# Fishboard.net
KiCad netlist of a schematic drawn in EAGLE
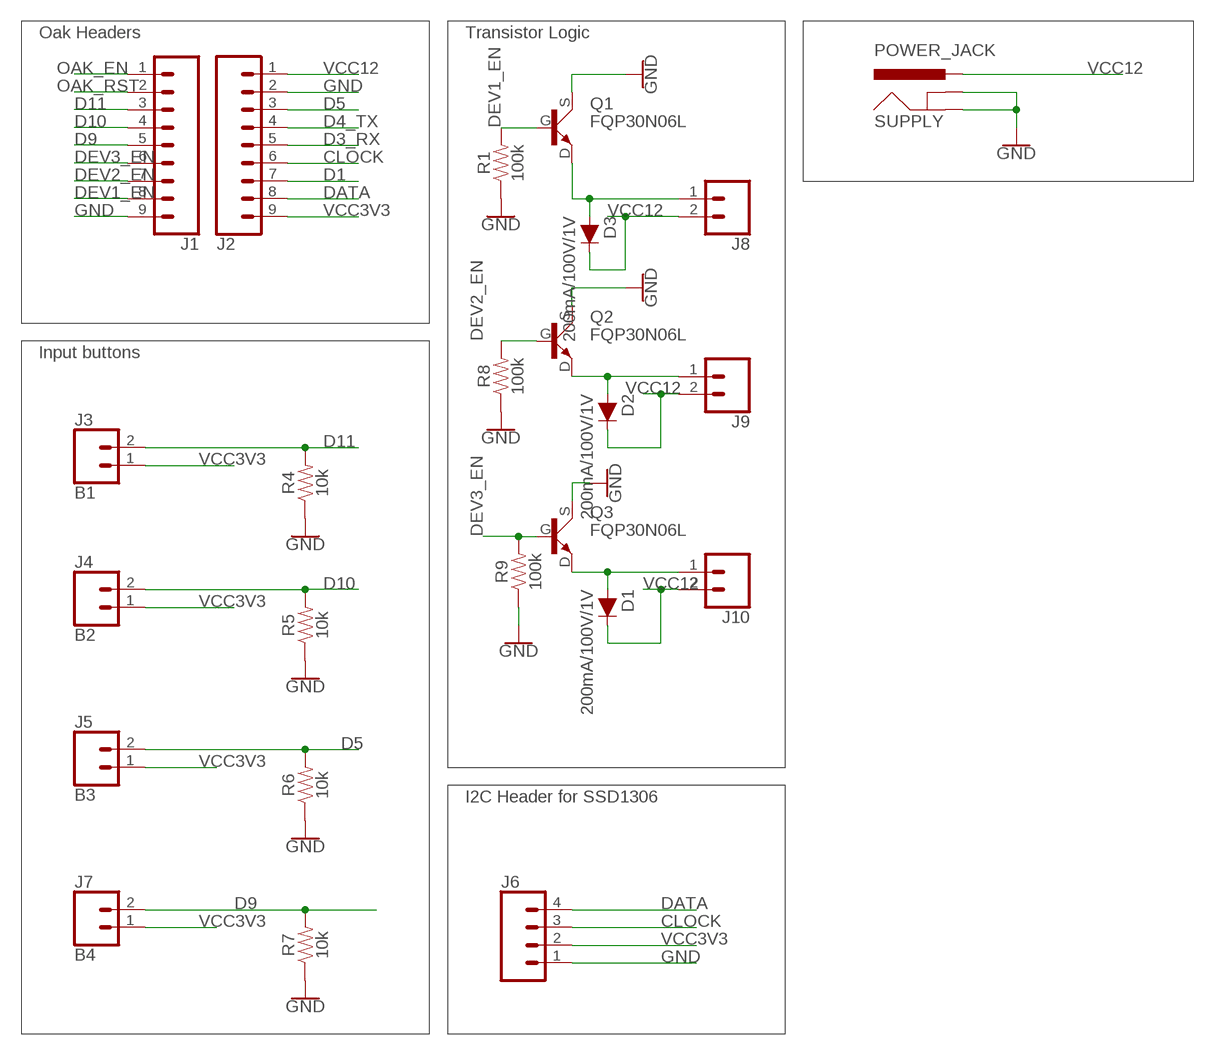
[diagram p0: schematic, sheet 1]

(export (version "E")
  (design (tool "Eeschema 10.0.6"))
  (components
    (comp (ref "D1")
      (value "200mA/100V/1V")
      (footprint "eagle-import:DIODE-1N4148-KIT")
      (libsource (lib "eagle-import") (part "DIODE-KIT"))
    )
    (comp (ref "D2")
      (value "200mA/100V/1V")
      (footprint "eagle-import:DIODE-1N4148-KIT")
      (libsource (lib "eagle-import") (part "DIODE-KIT"))
    )
    (comp (ref "D3")
      (value "200mA/100V/1V")
      (footprint "eagle-import:DIODE-1N4148-KIT")
      (libsource (lib "eagle-import") (part "DIODE-KIT"))
    )
    (comp (ref "J1")
      (value "CONN_09LOCK")
      (footprint "eagle-import:1X09_LOCK")
      (libsource (lib "eagle-import") (part "CONN_09LOCK"))
    )
    (comp (ref "J2")
      (value "CONN_09LOCK")
      (footprint "eagle-import:1X09_LOCK")
      (libsource (lib "eagle-import") (part "CONN_09LOCK"))
    )
    (comp (ref "J3")
      (value "B1")
      (footprint "eagle-import:1X02_LOCK")
      (libsource (lib "eagle-import") (part "CONN_02LOCK"))
    )
    (comp (ref "J4")
      (value "B2")
      (footprint "eagle-import:1X02_LOCK")
      (libsource (lib "eagle-import") (part "CONN_02LOCK"))
    )
    (comp (ref "J5")
      (value "B3")
      (footprint "eagle-import:1X02_LOCK")
      (libsource (lib "eagle-import") (part "CONN_02LOCK"))
    )
    (comp (ref "J6")
      (value "CONN_04LOCK")
      (footprint "eagle-import:1X04_LOCK")
      (libsource (lib "eagle-import") (part "CONN_04LOCK"))
    )
    (comp (ref "J7")
      (value "B4")
      (footprint "eagle-import:1X02_LOCK")
      (libsource (lib "eagle-import") (part "CONN_02LOCK"))
    )
    (comp (ref "J8")
      (value "CONN_02PTH3")
      (footprint "eagle-import:1X02_LONGPADS")
      (libsource (lib "eagle-import") (part "CONN_02PTH3"))
    )
    (comp (ref "J9")
      (value "CONN_02PTH3")
      (footprint "eagle-import:1X02_LONGPADS")
      (libsource (lib "eagle-import") (part "CONN_02PTH3"))
    )
    (comp (ref "J10")
      (value "CONN_02PTH3")
      (footprint "eagle-import:1X02_LONGPADS")
      (libsource (lib "eagle-import") (part "CONN_02PTH3"))
    )
    (comp (ref "Q1")
      (value "FQP30N06L")
      (footprint "eagle-import:TO220")
      (libsource (lib "eagle-import") (part "FQP30N06L"))
    )
    (comp (ref "Q2")
      (value "FQP30N06L")
      (footprint "eagle-import:TO220")
      (libsource (lib "eagle-import") (part "FQP30N06L"))
    )
    (comp (ref "Q3")
      (value "FQP30N06L")
      (footprint "eagle-import:TO220")
      (libsource (lib "eagle-import") (part "FQP30N06L"))
    )
    (comp (ref "R1")
      (value "100k")
      (footprint "eagle-import:AXIAL-0.3")
      (libsource (lib "eagle-import") (part "100KOHM-HORIZ-1/4W-5%"))
    )
    (comp (ref "R4")
      (value "10k")
      (footprint "eagle-import:AXIAL-0.3")
      (libsource (lib "eagle-import") (part "10KOHM-HORIZ-1/4W-1%"))
    )
    (comp (ref "R5")
      (value "10k")
      (footprint "eagle-import:AXIAL-0.3")
      (libsource (lib "eagle-import") (part "10KOHM-HORIZ-1/4W-1%"))
    )
    (comp (ref "R6")
      (value "10k")
      (footprint "eagle-import:AXIAL-0.3")
      (libsource (lib "eagle-import") (part "10KOHM-HORIZ-1/4W-1%"))
    )
    (comp (ref "R7")
      (value "10k")
      (footprint "eagle-import:AXIAL-0.3")
      (libsource (lib "eagle-import") (part "10KOHM-HORIZ-1/4W-1%"))
    )
    (comp (ref "R8")
      (value "100k")
      (footprint "eagle-import:AXIAL-0.3")
      (libsource (lib "eagle-import") (part "100KOHM-HORIZ-1/4W-5%"))
    )
    (comp (ref "R9")
      (value "100k")
      (footprint "eagle-import:AXIAL-0.3")
      (libsource (lib "eagle-import") (part "100KOHM-HORIZ-1/4W-5%"))
    )
    (comp (ref "SUPPLY")
      (value "POWER_JACK")
      (footprint "eagle-import:POWER_JACK_PTH")
      (libsource (lib "eagle-import") (part "POWER_JACK"))
    )
  )
  (nets
    (net (code "1") (name "/CLOCK") (class "Default")
      (node (ref "J2") (pin "6") (pinfunction "6_6") (pintype "passive"))
      (node (ref "J6") (pin "3") (pinfunction "3_3") (pintype "passive"))
    )
    (net (code "2") (name "/D1") (class "Default")
      (node (ref "J2") (pin "7") (pinfunction "7_7") (pintype "passive"))
    )
    (net (code "3") (name "/D3_RX") (class "Default")
      (node (ref "J2") (pin "5") (pinfunction "5_5") (pintype "passive"))
    )
    (net (code "4") (name "/D4_TX") (class "Default")
      (node (ref "J2") (pin "4") (pinfunction "4_4") (pintype "passive"))
    )
    (net (code "5") (name "/D5") (class "Default")
      (node (ref "J2") (pin "3") (pinfunction "3_3") (pintype "passive"))
      (node (ref "J5") (pin "2") (pinfunction "2_2") (pintype "passive"))
      (node (ref "R6") (pin "P$2") (pinfunction "2_P$2") (pintype "passive"))
    )
    (net (code "6") (name "/D9") (class "Default")
      (node (ref "J1") (pin "5") (pinfunction "5_5") (pintype "passive"))
      (node (ref "J7") (pin "2") (pinfunction "2_2") (pintype "passive"))
      (node (ref "R7") (pin "P$2") (pinfunction "2_P$2") (pintype "passive"))
    )
    (net (code "7") (name "/D10") (class "Default")
      (node (ref "J1") (pin "4") (pinfunction "4_4") (pintype "passive"))
      (node (ref "J4") (pin "2") (pinfunction "2_2") (pintype "passive"))
      (node (ref "R5") (pin "P$2") (pinfunction "2_P$2") (pintype "passive"))
    )
    (net (code "8") (name "/D11") (class "Default")
      (node (ref "J1") (pin "3") (pinfunction "3_3") (pintype "passive"))
      (node (ref "J3") (pin "2") (pinfunction "2_2") (pintype "passive"))
      (node (ref "R4") (pin "P$2") (pinfunction "2_P$2") (pintype "passive"))
    )
    (net (code "9") (name "/DATA") (class "Default")
      (node (ref "J2") (pin "8") (pinfunction "8_8") (pintype "passive"))
      (node (ref "J6") (pin "4") (pinfunction "4_4") (pintype "passive"))
    )
    (net (code "10") (name "/DEV1_EN") (class "Default")
      (node (ref "J1") (pin "8") (pinfunction "8_8") (pintype "passive"))
      (node (ref "Q1") (pin "G") (pinfunction "1_G") (pintype "passive"))
      (node (ref "R1") (pin "P$2") (pinfunction "2_P$2") (pintype "passive"))
    )
    (net (code "11") (name "/DEV2_EN") (class "Default")
      (node (ref "J1") (pin "7") (pinfunction "7_7") (pintype "passive"))
      (node (ref "Q2") (pin "G") (pinfunction "1_G") (pintype "passive"))
      (node (ref "R8") (pin "P$2") (pinfunction "2_P$2") (pintype "passive"))
    )
    (net (code "12") (name "/DEV3_EN") (class "Default")
      (node (ref "J1") (pin "6") (pinfunction "6_6") (pintype "passive"))
      (node (ref "Q3") (pin "G") (pinfunction "1_G") (pintype "passive"))
      (node (ref "R9") (pin "P$2") (pinfunction "2_P$2") (pintype "passive"))
    )
    (net (code "13") (name "/OAK_EN") (class "Default")
      (node (ref "J1") (pin "1") (pinfunction "1_1") (pintype "passive"))
    )
    (net (code "14") (name "/OAK_RST") (class "Default")
      (node (ref "J1") (pin "2") (pinfunction "2_2") (pintype "passive"))
    )
    (net (code "15") (name "/VCC3V3") (class "Default")
      (node (ref "J2") (pin "9") (pinfunction "9_9") (pintype "passive"))
      (node (ref "J3") (pin "1") (pinfunction "1_1") (pintype "passive"))
      (node (ref "J4") (pin "1") (pinfunction "1_1") (pintype "passive"))
      (node (ref "J5") (pin "1") (pinfunction "1_1") (pintype "passive"))
      (node (ref "J6") (pin "2") (pinfunction "2_2") (pintype "passive"))
      (node (ref "J7") (pin "1") (pinfunction "1_1") (pintype "passive"))
    )
    (net (code "16") (name "/VCC12") (class "Default")
      (node (ref "D1") (pin "C") (pinfunction "C_C") (pintype "passive"))
      (node (ref "D2") (pin "C") (pinfunction "C_C") (pintype "passive"))
      (node (ref "D3") (pin "C") (pinfunction "C_C") (pintype "passive"))
      (node (ref "J10") (pin "2") (pinfunction "2_2") (pintype "passive"))
      (node (ref "J2") (pin "1") (pinfunction "1_1") (pintype "passive"))
      (node (ref "J8") (pin "2") (pinfunction "2_2") (pintype "passive"))
      (node (ref "J9") (pin "2") (pinfunction "2_2") (pintype "passive"))
      (node (ref "SUPPLY") (pin "PWR") (pinfunction "PWR_PWR") (pintype "bidirectional"))
    )
    (net (code "17") (name "GND") (class "Default")
      (node (ref "J1") (pin "9") (pinfunction "9_9") (pintype "passive"))
      (node (ref "J2") (pin "2") (pinfunction "2_2") (pintype "passive"))
      (node (ref "J6") (pin "1") (pinfunction "1_1") (pintype "passive"))
      (node (ref "Q1") (pin "S") (pinfunction "3_S") (pintype "passive"))
      (node (ref "Q2") (pin "S") (pinfunction "3_S") (pintype "passive"))
      (node (ref "Q3") (pin "S") (pinfunction "3_S") (pintype "passive"))
      (node (ref "R1") (pin "P$1") (pinfunction "1_P$1") (pintype "passive"))
      (node (ref "R4") (pin "P$1") (pinfunction "1_P$1") (pintype "passive"))
      (node (ref "R5") (pin "P$1") (pinfunction "1_P$1") (pintype "passive"))
      (node (ref "R6") (pin "P$1") (pinfunction "1_P$1") (pintype "passive"))
      (node (ref "R7") (pin "P$1") (pinfunction "1_P$1") (pintype "passive"))
      (node (ref "R8") (pin "P$1") (pinfunction "1_P$1") (pintype "passive"))
      (node (ref "R9") (pin "P$1") (pinfunction "1_P$1") (pintype "passive"))
      (node (ref "SUPPLY") (pin "GND") (pinfunction "GND_GND") (pintype "bidirectional"))
      (node (ref "SUPPLY") (pin "GNDBREAK") (pinfunction "GNDBREAK_GNDBREAK") (pintype "bidirectional"))
    )
    (net (code "18") (name "Net-(Q1-2)") (class "Default")
      (node (ref "D3") (pin "A") (pinfunction "A_A") (pintype "passive"))
      (node (ref "J8") (pin "1") (pinfunction "1_1") (pintype "passive"))
      (node (ref "Q1") (pin "D") (pinfunction "2_D") (pintype "passive"))
    )
    (net (code "19") (name "Net-(Q2-2)") (class "Default")
      (node (ref "D2") (pin "A") (pinfunction "A_A") (pintype "passive"))
      (node (ref "J9") (pin "1") (pinfunction "1_1") (pintype "passive"))
      (node (ref "Q2") (pin "D") (pinfunction "2_D") (pintype "passive"))
    )
    (net (code "20") (name "Net-(Q3-2)") (class "Default")
      (node (ref "D1") (pin "A") (pinfunction "A_A") (pintype "passive"))
      (node (ref "J10") (pin "1") (pinfunction "1_1") (pintype "passive"))
      (node (ref "Q3") (pin "D") (pinfunction "2_D") (pintype "passive"))
    )
  )
)
